# Tutorial1.net
KiCad netlist of a schematic drawn in EAGLE
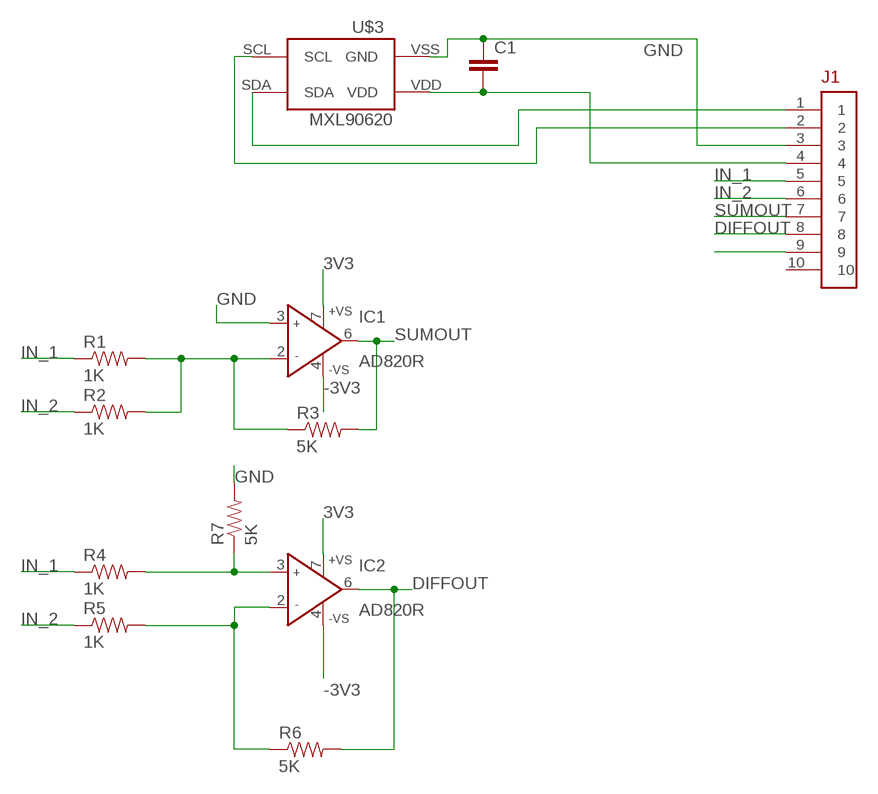
[diagram p0: schematic, sheet 1]

(export (version "E")
  (design (tool "Eeschema 10.0.6"))
  (components
    (comp (ref "C1")
      (value "CAP0805")
      (footprint "eagle-import:0805")
      (libsource (lib "eagle-import") (part "CAP0805"))
    )
    (comp (ref "IC1")
      (value "AD820R")
      (footprint "eagle-import:SO8")
      (libsource (lib "eagle-import") (part "AD820R"))
    )
    (comp (ref "IC2")
      (value "AD820R")
      (footprint "eagle-import:SO8")
      (libsource (lib "eagle-import") (part "AD820R"))
    )
    (comp (ref "J1")
      (value "M50-3120545")
      (footprint "eagle-import:10PINFEMALE")
      (libsource (lib "eagle-import") (part "M50-3120545"))
    )
    (comp (ref "R1")
      (value "1K")
      (footprint "eagle-import:0805")
      (libsource (lib "eagle-import") (part "RESISTOR"))
    )
    (comp (ref "R2")
      (value "1K")
      (footprint "eagle-import:0805")
      (libsource (lib "eagle-import") (part "RESISTOR"))
    )
    (comp (ref "R3")
      (value "5K")
      (footprint "eagle-import:0805")
      (libsource (lib "eagle-import") (part "RESISTOR"))
    )
    (comp (ref "R4")
      (value "1K")
      (footprint "eagle-import:0805")
      (libsource (lib "eagle-import") (part "RESISTOR"))
    )
    (comp (ref "R5")
      (value "1K")
      (footprint "eagle-import:0805")
      (libsource (lib "eagle-import") (part "RESISTOR"))
    )
    (comp (ref "R6")
      (value "5K")
      (footprint "eagle-import:0805")
      (libsource (lib "eagle-import") (part "RESISTOR"))
    )
    (comp (ref "R7")
      (value "5K")
      (footprint "eagle-import:0805")
      (libsource (lib "eagle-import") (part "RESISTOR"))
    )
    (comp (ref "U$3")
      (value "MXL90620")
      (footprint "eagle-import:MXL90620")
      (libsource (lib "eagle-import") (part "MXL90620"))
    )
  )
  (nets
    (net (code "1") (name "/-3V3") (class "Default")
      (node (ref "IC1") (pin "4") (pinfunction "-VS_4") (pintype "input"))
      (node (ref "IC2") (pin "4") (pinfunction "-VS_4") (pintype "input"))
      (node (ref "J1") (pin "9") (pinfunction "9_9") (pintype "bidirectional"))
    )
    (net (code "2") (name "/3V3") (class "Default")
      (node (ref "C1") (pin "2") (pinfunction "2_2") (pintype "passive"))
      (node (ref "IC1") (pin "7") (pinfunction "+VS_7") (pintype "input"))
      (node (ref "IC2") (pin "7") (pinfunction "+VS_7") (pintype "input"))
      (node (ref "J1") (pin "4") (pinfunction "4_4") (pintype "bidirectional"))
      (node (ref "U$3") (pin "VDD") (pinfunction "VDD_VDD") (pintype "bidirectional"))
    )
    (net (code "3") (name "/DIFFOUT") (class "Default")
      (node (ref "IC2") (pin "6") (pinfunction "OUT_6") (pintype "output"))
      (node (ref "J1") (pin "8") (pinfunction "8_8") (pintype "bidirectional"))
      (node (ref "R6") (pin "2") (pinfunction "2_2") (pintype "passive"))
    )
    (net (code "4") (name "/GND") (class "Default")
      (node (ref "C1") (pin "1") (pinfunction "1_1") (pintype "passive"))
      (node (ref "IC1") (pin "3") (pinfunction "IN+_3") (pintype "input"))
      (node (ref "J1") (pin "3") (pinfunction "3_3") (pintype "bidirectional"))
      (node (ref "R7") (pin "2") (pinfunction "2_2") (pintype "passive"))
      (node (ref "U$3") (pin "VSS") (pinfunction "GND_VSS") (pintype "bidirectional"))
    )
    (net (code "5") (name "/IN_1") (class "Default")
      (node (ref "J1") (pin "5") (pinfunction "5_5") (pintype "bidirectional"))
      (node (ref "R1") (pin "1") (pinfunction "1_1") (pintype "passive"))
      (node (ref "R4") (pin "1") (pinfunction "1_1") (pintype "passive"))
    )
    (net (code "6") (name "/IN_2") (class "Default")
      (node (ref "J1") (pin "6") (pinfunction "6_6") (pintype "bidirectional"))
      (node (ref "R2") (pin "1") (pinfunction "1_1") (pintype "passive"))
      (node (ref "R5") (pin "1") (pinfunction "1_1") (pintype "passive"))
    )
    (net (code "7") (name "/SUMOUT") (class "Default")
      (node (ref "IC1") (pin "6") (pinfunction "OUT_6") (pintype "output"))
      (node (ref "J1") (pin "7") (pinfunction "7_7") (pintype "bidirectional"))
      (node (ref "R3") (pin "2") (pinfunction "2_2") (pintype "passive"))
    )
    (net (code "8") (name "Net-(IC1-IN-)") (class "Default")
      (node (ref "IC1") (pin "2") (pinfunction "IN-_2") (pintype "input"))
      (node (ref "R1") (pin "2") (pinfunction "2_2") (pintype "passive"))
      (node (ref "R2") (pin "2") (pinfunction "2_2") (pintype "passive"))
      (node (ref "R3") (pin "1") (pinfunction "1_1") (pintype "passive"))
    )
    (net (code "9") (name "Net-(IC2-IN+)") (class "Default")
      (node (ref "IC2") (pin "3") (pinfunction "IN+_3") (pintype "input"))
      (node (ref "R4") (pin "2") (pinfunction "2_2") (pintype "passive"))
      (node (ref "R7") (pin "1") (pinfunction "1_1") (pintype "passive"))
    )
    (net (code "10") (name "Net-(IC2-IN-)") (class "Default")
      (node (ref "IC2") (pin "2") (pinfunction "IN-_2") (pintype "input"))
      (node (ref "R5") (pin "2") (pinfunction "2_2") (pintype "passive"))
      (node (ref "R6") (pin "1") (pinfunction "1_1") (pintype "passive"))
    )
    (net (code "11") (name "Net-(J1-Pad1)") (class "Default")
      (node (ref "J1") (pin "1") (pinfunction "1_1") (pintype "bidirectional"))
      (node (ref "U$3") (pin "SDA") (pinfunction "SDA_SDA") (pintype "bidirectional"))
    )
    (net (code "12") (name "Net-(J1-Pad2)") (class "Default")
      (node (ref "J1") (pin "2") (pinfunction "2_2") (pintype "bidirectional"))
      (node (ref "U$3") (pin "SCL") (pinfunction "SCL_SCL") (pintype "bidirectional"))
    )
    (net (code "13") (name "unconnected-(J1-Pad10)") (class "Default")
      (node (ref "J1") (pin "10") (pinfunction "10_10") (pintype "bidirectional"))
    )
  )
)
